# Amp_Test_7_2_4.net
KiCad netlist of a schematic drawn in EAGLE
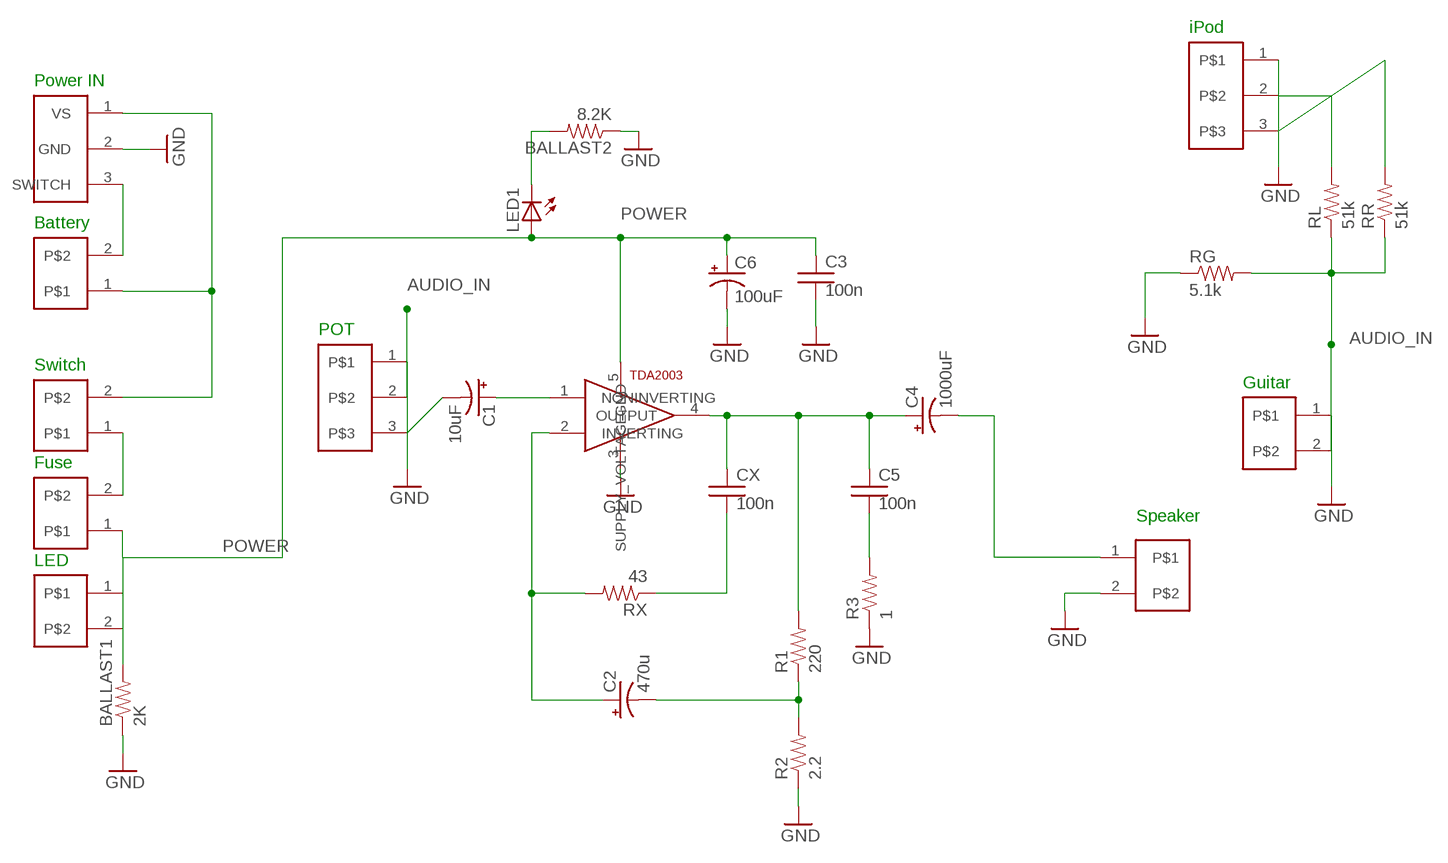
[diagram p0: schematic, sheet 1]

(export (version "E")
  (design (tool "Eeschema 10.0.6"))
  (components
    (comp (ref "BALLAST1")
      (value "2K")
      (footprint "eagle-import:RESISTOR_1_4W")
      (libsource (lib "eagle-import") (part "RESISTOR"))
    )
    (comp (ref "BALLAST2")
      (value "8.2K")
      (footprint "eagle-import:RESISTOR_1_4W")
      (libsource (lib "eagle-import") (part "RESISTOR"))
    )
    (comp (ref "BATTERY")
      (value "M02")
      (footprint "eagle-import:SCREW_TERMINAL_2_5MM")
      (libsource (lib "eagle-import") (part "M02"))
    )
    (comp (ref "C1")
      (value "10uF")
      (footprint "eagle-import:CAP_POL_5MMD_5MML")
      (libsource (lib "eagle-import") (part "CAP_POL5MMD_5MML"))
    )
    (comp (ref "C2")
      (value "470u")
      (footprint "eagle-import:CAP_POL_8MMD_5MMP")
      (libsource (lib "eagle-import") (part "CAP_POLCAP_POL_8MMD_5MMP"))
    )
    (comp (ref "C3")
      (value "100n")
      (footprint "eagle-import:CAP_5MM")
      (libsource (lib "eagle-import") (part "CAP_5MM"))
    )
    (comp (ref "C4")
      (value "1000uF")
      (footprint "eagle-import:CAP_POL_10MMD_5MMP")
      (libsource (lib "eagle-import") (part "CAP_POL10MMD_5MML"))
    )
    (comp (ref "C5")
      (value "100n")
      (footprint "eagle-import:CAP_5MM")
      (libsource (lib "eagle-import") (part "CAP_5MM"))
    )
    (comp (ref "C6")
      (value "100uF")
      (footprint "eagle-import:CAP_POL_5MMD_5MML")
      (libsource (lib "eagle-import") (part "CAP_POL5MMD_5MML"))
    )
    (comp (ref "CX")
      (value "100n")
      (footprint "eagle-import:CAP_5MM")
      (libsource (lib "eagle-import") (part "CAP_5MM"))
    )
    (comp (ref "FUSE")
      (value "M02")
      (footprint "eagle-import:SCREW_TERMINAL_2_5MM")
      (libsource (lib "eagle-import") (part "M02"))
    )
    (comp (ref "GUITAR")
      (value "M02")
      (footprint "eagle-import:SCREW_TERMINAL_2_5MM")
      (libsource (lib "eagle-import") (part "M02"))
    )
    (comp (ref "IPOD")
      (value "M03")
      (footprint "eagle-import:SCREW_TERMINAL_2_5MM_3")
      (libsource (lib "eagle-import") (part "M03"))
    )
    (comp (ref "LED")
      (value "M02")
      (footprint "eagle-import:SCREW_TERMINAL_2_5MM")
      (libsource (lib "eagle-import") (part "M02"))
    )
    (comp (ref "LED1")
      (value "LED3MM")
      (footprint "eagle-import:LED3MM")
      (libsource (lib "eagle-import") (part "LED3MM"))
    )
    (comp (ref "POT")
      (value "M03")
      (footprint "eagle-import:SCREW_TERMINAL_2_5MM_3")
      (libsource (lib "eagle-import") (part "M03"))
    )
    (comp (ref "POWER_IN")
      (value "DC_POWER_M03")
      (footprint "eagle-import:SCREW_TERMINAL_2_5MM_3")
      (libsource (lib "eagle-import") (part "DC_POWER_M03"))
    )
    (comp (ref "R1")
      (value "220")
      (footprint "eagle-import:RESISTOR_1_4W")
      (libsource (lib "eagle-import") (part "RESISTOR"))
    )
    (comp (ref "R2")
      (value "2.2")
      (footprint "eagle-import:RESISTOR_1_4W")
      (libsource (lib "eagle-import") (part "RESISTOR"))
    )
    (comp (ref "R3")
      (value "1")
      (footprint "eagle-import:RESISTOR_1_4W")
      (libsource (lib "eagle-import") (part "RESISTOR"))
    )
    (comp (ref "RG")
      (value "5.1k")
      (footprint "eagle-import:RESISTOR_1_4W")
      (libsource (lib "eagle-import") (part "RESISTOR"))
    )
    (comp (ref "RL")
      (value "51k")
      (footprint "eagle-import:RESISTOR_1_4W")
      (libsource (lib "eagle-import") (part "RESISTOR"))
    )
    (comp (ref "RR")
      (value "51k")
      (footprint "eagle-import:RESISTOR_1_4W")
      (libsource (lib "eagle-import") (part "RESISTOR"))
    )
    (comp (ref "RX")
      (value "43")
      (footprint "eagle-import:RESISTOR_1_4W")
      (libsource (lib "eagle-import") (part "RESISTOR"))
    )
    (comp (ref "SPEAKER")
      (value "M02")
      (footprint "eagle-import:SCREW_TERMINAL_2_5MM")
      (libsource (lib "eagle-import") (part "M02"))
    )
    (comp (ref "SWITCH")
      (value "M02")
      (footprint "eagle-import:SCREW_TERMINAL_2_5MM")
      (libsource (lib "eagle-import") (part "M02"))
    )
    (comp (ref "TDA2003")
      (value "TDA2003APENTAWATT")
      (footprint "eagle-import:PENTAWATT")
      (libsource (lib "eagle-import") (part "TDA2003APENTAWATT"))
    )
  )
  (nets
    (net (code "1") (name "/AUDIO_IN") (class "Default")
      (node (ref "GUITAR") (pin "2") (pinfunction "P$2_2") (pintype "bidirectional"))
      (node (ref "POT") (pin "2") (pinfunction "P$2_2") (pintype "bidirectional"))
      (node (ref "RG") (pin "P$2") (pinfunction "2_P$2") (pintype "passive"))
      (node (ref "RL") (pin "P$1") (pinfunction "1_P$1") (pintype "passive"))
      (node (ref "RR") (pin "P$1") (pinfunction "1_P$1") (pintype "passive"))
    )
    (net (code "2") (name "/POWER") (class "Default")
      (node (ref "C3") (pin "P$1") (pinfunction "P$1_P$1") (pintype "passive"))
      (node (ref "C6") (pin "+") (pinfunction "+_+") (pintype "passive"))
      (node (ref "FUSE") (pin "1") (pinfunction "P$1_1") (pintype "bidirectional"))
      (node (ref "LED") (pin "2") (pinfunction "P$2_2") (pintype "bidirectional"))
      (node (ref "LED1") (pin "A") (pinfunction "A_A") (pintype "passive"))
      (node (ref "TDA2003") (pin "5") (pinfunction "SUPPLY_VOLTAGE_5") (pintype "power_in"))
    )
    (net (code "3") (name "GND") (class "Default")
      (node (ref "BALLAST1") (pin "P$1") (pinfunction "1_P$1") (pintype "passive"))
      (node (ref "BALLAST2") (pin "P$1") (pinfunction "1_P$1") (pintype "passive"))
      (node (ref "C3") (pin "P$2") (pinfunction "P$2_P$2") (pintype "passive"))
      (node (ref "C6") (pin "-") (pinfunction "-_-") (pintype "passive"))
      (node (ref "GUITAR") (pin "1") (pinfunction "P$1_1") (pintype "bidirectional"))
      (node (ref "IPOD") (pin "1") (pinfunction "P$1_1") (pintype "bidirectional"))
      (node (ref "POT") (pin "1") (pinfunction "P$1_1") (pintype "bidirectional"))
      (node (ref "POWER_IN") (pin "2") (pinfunction "GND_2") (pintype "bidirectional"))
      (node (ref "R2") (pin "P$1") (pinfunction "1_P$1") (pintype "passive"))
      (node (ref "R3") (pin "P$1") (pinfunction "1_P$1") (pintype "passive"))
      (node (ref "RG") (pin "P$1") (pinfunction "1_P$1") (pintype "passive"))
      (node (ref "SPEAKER") (pin "2") (pinfunction "P$2_2") (pintype "bidirectional"))
      (node (ref "TDA2003") (pin "3") (pinfunction "GND_3") (pintype "power_in"))
    )
    (net (code "4") (name "Net-(BALLAST1-2)") (class "Default")
      (node (ref "BALLAST1") (pin "P$2") (pinfunction "2_P$2") (pintype "passive"))
      (node (ref "LED") (pin "1") (pinfunction "P$1_1") (pintype "bidirectional"))
    )
    (net (code "5") (name "Net-(BALLAST2-2)") (class "Default")
      (node (ref "BALLAST2") (pin "P$2") (pinfunction "2_P$2") (pintype "passive"))
      (node (ref "LED1") (pin "K") (pinfunction "C_K") (pintype "passive"))
    )
    (net (code "6") (name "Net-(BATTERY-P$1)") (class "Default")
      (node (ref "BATTERY") (pin "1") (pinfunction "P$1_1") (pintype "bidirectional"))
      (node (ref "POWER_IN") (pin "1") (pinfunction "VS_1") (pintype "bidirectional"))
      (node (ref "SWITCH") (pin "2") (pinfunction "P$2_2") (pintype "bidirectional"))
    )
    (net (code "7") (name "Net-(BATTERY-P$2)") (class "Default")
      (node (ref "BATTERY") (pin "2") (pinfunction "P$2_2") (pintype "bidirectional"))
      (node (ref "POWER_IN") (pin "3") (pinfunction "SWITCH_3") (pintype "bidirectional"))
    )
    (net (code "8") (name "Net-(C2-+)") (class "Default")
      (node (ref "C2") (pin "P$1") (pinfunction "+_P$1") (pintype "passive"))
      (node (ref "RX") (pin "P$2") (pinfunction "2_P$2") (pintype "passive"))
      (node (ref "TDA2003") (pin "2") (pinfunction "INVERTING_2") (pintype "input"))
    )
    (net (code "9") (name "Net-(C2--)") (class "Default")
      (node (ref "C2") (pin "P$2") (pinfunction "-_P$2") (pintype "passive"))
      (node (ref "R1") (pin "P$1") (pinfunction "1_P$1") (pintype "passive"))
      (node (ref "R2") (pin "P$2") (pinfunction "2_P$2") (pintype "passive"))
    )
    (net (code "10") (name "Net-(FUSE-P$2)") (class "Default")
      (node (ref "FUSE") (pin "2") (pinfunction "P$2_2") (pintype "bidirectional"))
      (node (ref "SWITCH") (pin "1") (pinfunction "P$1_1") (pintype "bidirectional"))
    )
    (net (code "11") (name "Net-(IPOD-P$2)") (class "Default")
      (node (ref "IPOD") (pin "2") (pinfunction "P$2_2") (pintype "bidirectional"))
      (node (ref "RL") (pin "P$2") (pinfunction "2_P$2") (pintype "passive"))
    )
    (net (code "12") (name "Net-(IPOD-P$3)") (class "Default")
      (node (ref "IPOD") (pin "3") (pinfunction "P$3_3") (pintype "bidirectional"))
      (node (ref "RR") (pin "P$2") (pinfunction "2_P$2") (pintype "passive"))
    )
    (net (code "13") (name "Net-(POT-P$3)") (class "Default")
      (node (ref "C1") (pin "-") (pinfunction "-_-") (pintype "passive"))
      (node (ref "POT") (pin "3") (pinfunction "P$3_3") (pintype "bidirectional"))
    )
    (net (code "14") (name "Net-(R1-2)") (class "Default")
      (node (ref "C4") (pin "+") (pinfunction "+_+") (pintype "passive"))
      (node (ref "C5") (pin "P$1") (pinfunction "P$1_P$1") (pintype "passive"))
      (node (ref "CX") (pin "P$1") (pinfunction "P$1_P$1") (pintype "passive"))
      (node (ref "R1") (pin "P$2") (pinfunction "2_P$2") (pintype "passive"))
      (node (ref "TDA2003") (pin "4") (pinfunction "OUTPUT_4") (pintype "output"))
    )
    (net (code "15") (name "Net-(R3-2)") (class "Default")
      (node (ref "C5") (pin "P$2") (pinfunction "P$2_P$2") (pintype "passive"))
      (node (ref "R3") (pin "P$2") (pinfunction "2_P$2") (pintype "passive"))
    )
    (net (code "16") (name "Net-(RX-1)") (class "Default")
      (node (ref "CX") (pin "P$2") (pinfunction "P$2_P$2") (pintype "passive"))
      (node (ref "RX") (pin "P$1") (pinfunction "1_P$1") (pintype "passive"))
    )
    (net (code "17") (name "Net-(SPEAKER-P$1)") (class "Default")
      (node (ref "C4") (pin "-") (pinfunction "-_-") (pintype "passive"))
      (node (ref "SPEAKER") (pin "1") (pinfunction "P$1_1") (pintype "bidirectional"))
    )
    (net (code "18") (name "Net-(TDA2003-NONINVERTING)") (class "Default")
      (node (ref "C1") (pin "+") (pinfunction "+_+") (pintype "passive"))
      (node (ref "TDA2003") (pin "1") (pinfunction "NONINVERTING_1") (pintype "input"))
    )
  )
)
